# XC95144XL_DEVBOARD.net
KiCad netlist of a schematic drawn in Altium Designer
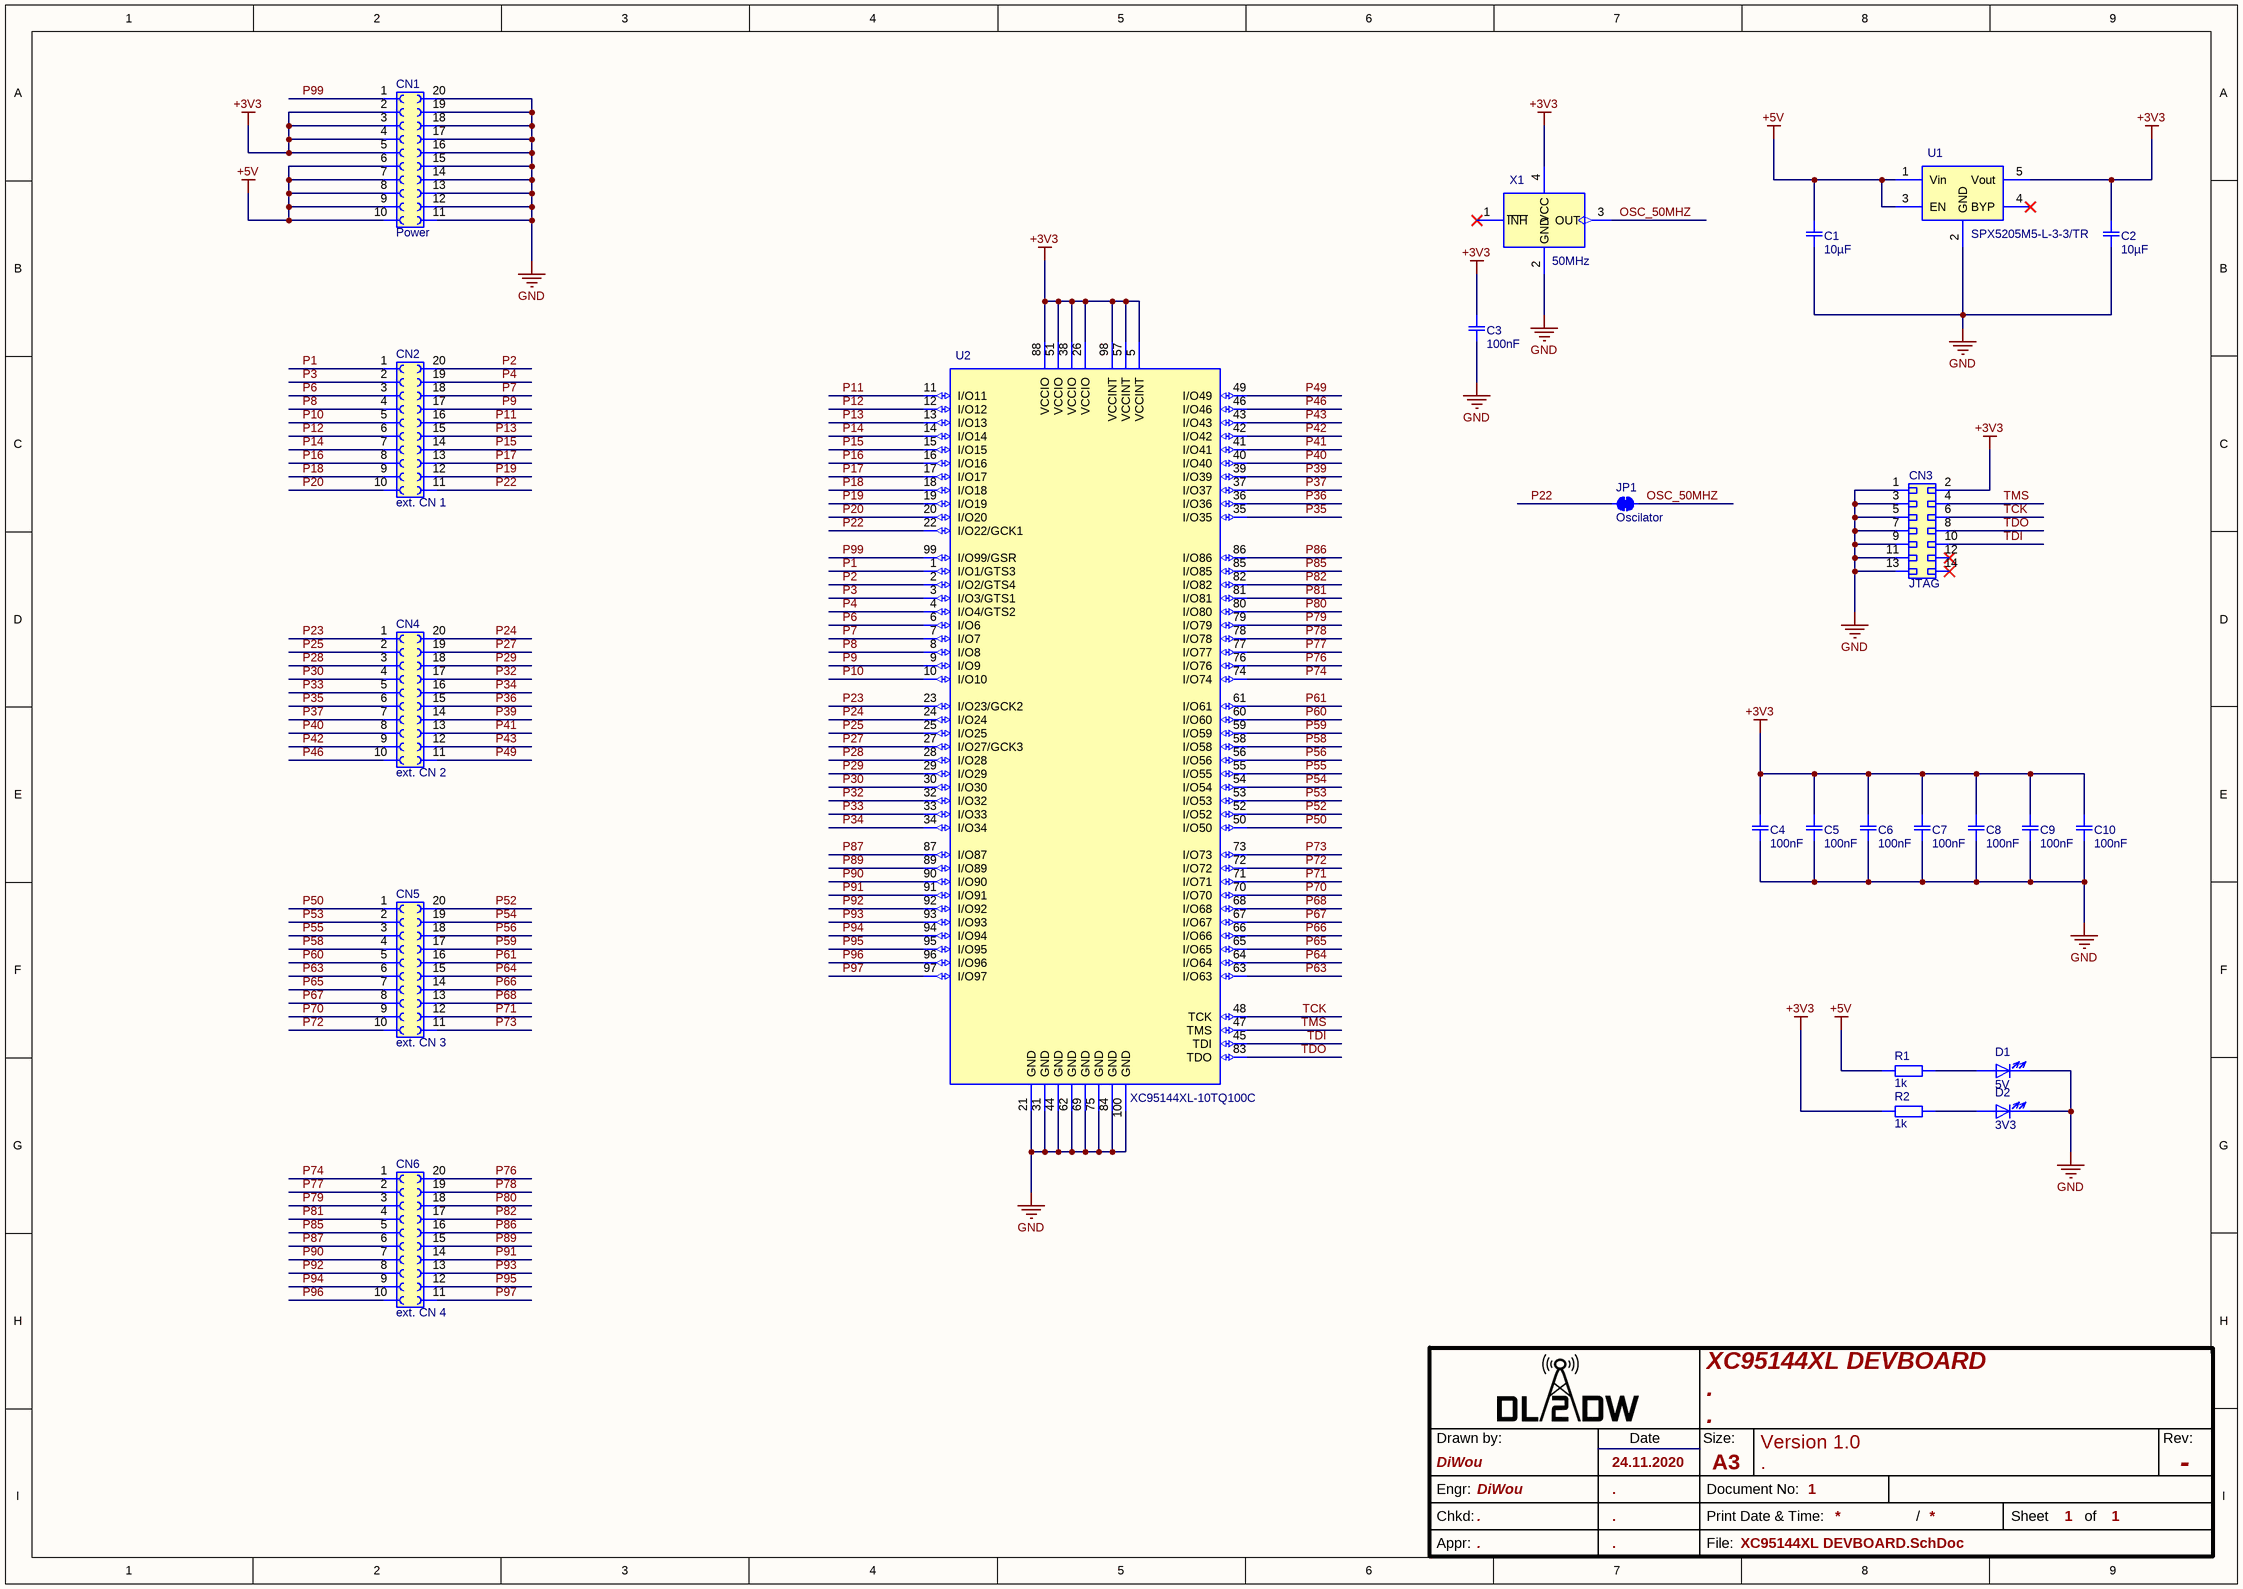
[diagram p0: XC95144XL DEVBOARD.SchDoc]

(export (version "E")
  (design (tool "Eeschema 10.0.6"))
  (components
    (comp (ref "C1")
      (value "10µF")
      (footprint "Kemet C0805CxxxK8RACTU Series H=1.4mm")
      (description "KEMET - C0805C106K8RACTU - CAP, 10µF, 10V, 10%, X7R, 0805")
      (fields (field (name "VOLTAGE") "10V") (field (name "TOLERANCE") "10%"))
      (libsource (lib "PCB-Tech Cloud") (part "Capacitor"))
    )
    (comp (ref "C2")
      (value "10µF")
      (footprint "Kemet C0805CxxxK8RACTU Series H=1.4mm")
      (description "KEMET - C0805C106K8RACTU - CAP, 10µF, 10V, 10%, X7R, 0805")
      (fields (field (name "VOLTAGE") "10V") (field (name "TOLERANCE") "10%"))
      (libsource (lib "PCB-Tech Cloud") (part "Capacitor"))
    )
    (comp (ref "C3")
      (value "100nF")
      (footprint "CAP 100nF SMD 0603 C0603C104J3RACTU")
      (fields (field (name "TOLERANCE") "5%") (field (name "VOLTAGE") "25V"))
      (libsource (lib "PCB-Tech Cloud") (part "Capacitor"))
    )
    (comp (ref "C4")
      (value "100nF")
      (footprint "CAP 100nF SMD 0603 C0603C104J3RACTU")
      (fields (field (name "TOLERANCE") "5%") (field (name "VOLTAGE") "25V"))
      (libsource (lib "PCB-Tech Cloud") (part "Capacitor"))
    )
    (comp (ref "C5")
      (value "100nF")
      (footprint "CAP 100nF SMD 0603 C0603C104J3RACTU")
      (fields (field (name "TOLERANCE") "5%") (field (name "VOLTAGE") "25V"))
      (libsource (lib "PCB-Tech Cloud") (part "Capacitor"))
    )
    (comp (ref "C6")
      (value "100nF")
      (footprint "CAP 100nF SMD 0603 C0603C104J3RACTU")
      (fields (field (name "TOLERANCE") "5%") (field (name "VOLTAGE") "25V"))
      (libsource (lib "PCB-Tech Cloud") (part "Capacitor"))
    )
    (comp (ref "C7")
      (value "100nF")
      (footprint "CAP 100nF SMD 0603 C0603C104J3RACTU")
      (fields (field (name "TOLERANCE") "5%") (field (name "VOLTAGE") "25V"))
      (libsource (lib "PCB-Tech Cloud") (part "Capacitor"))
    )
    (comp (ref "C8")
      (value "100nF")
      (footprint "CAP 100nF SMD 0603 C0603C104J3RACTU")
      (fields (field (name "TOLERANCE") "5%") (field (name "VOLTAGE") "25V"))
      (libsource (lib "PCB-Tech Cloud") (part "Capacitor"))
    )
    (comp (ref "C9")
      (value "100nF")
      (footprint "CAP 100nF SMD 0603 C0603C104J3RACTU")
      (fields (field (name "TOLERANCE") "5%") (field (name "VOLTAGE") "25V"))
      (libsource (lib "PCB-Tech Cloud") (part "Capacitor"))
    )
    (comp (ref "C10")
      (value "100nF")
      (footprint "CAP 100nF SMD 0603 C0603C104J3RACTU")
      (fields (field (name "TOLERANCE") "5%") (field (name "VOLTAGE") "25V"))
      (libsource (lib "PCB-Tech Cloud") (part "Capacitor"))
    )
    (comp (ref "CN1")
      (value "Power")
      (footprint "Female Pin Header 02x10 Straight P2.54mm H8.5mm")
      (description "Headers & Wire Housings 10+10 VERT SOCKET DIL")
      (libsource (lib "PCB-Tech Cloud") (part "CONN Female 02x10"))
    )
    (comp (ref "CN2")
      (value "ext. CN 1")
      (footprint "Female Pin Header 02x10 Straight P2.54mm H8.5mm")
      (description "Headers & Wire Housings 10+10 VERT SOCKET DIL")
      (libsource (lib "PCB-Tech Cloud") (part "CONN Female 02x10"))
    )
    (comp (ref "CN3")
      (value "JTAG")
      (footprint "IDC Header 2x7 P2.54mm Straight")
      (description "Conn Shrouded Header HDR 14 POS 2.54mm Solder ST Thru-Hole")
      (libsource (lib "PCB-Tech Cloud") (part "CONN 02x07 Odd Even"))
    )
    (comp (ref "CN4")
      (value "ext. CN 2")
      (footprint "Female Pin Header 02x10 Straight P2.54mm H8.5mm")
      (description "Headers & Wire Housings 10+10 VERT SOCKET DIL")
      (libsource (lib "PCB-Tech Cloud") (part "CONN Female 02x10"))
    )
    (comp (ref "CN5")
      (value "ext. CN 3")
      (footprint "Female Pin Header 02x10 Straight P2.54mm H8.5mm")
      (description "Headers & Wire Housings 10+10 VERT SOCKET DIL")
      (libsource (lib "PCB-Tech Cloud") (part "CONN Female 02x10"))
    )
    (comp (ref "CN6")
      (value "ext. CN 4")
      (footprint "Female Pin Header 02x10 Straight P2.54mm H8.5mm")
      (description "Headers & Wire Housings 10+10 VERT SOCKET DIL")
      (libsource (lib "PCB-Tech Cloud") (part "CONN Female 02x10"))
    )
    (comp (ref "D1")
      (value "5V")
      (footprint "LED Red SMD 0603")
      (description "LED RED DIFFUSED 0603 SMD")
      (libsource (lib "PCB-Tech Cloud") (part "LED Standard"))
    )
    (comp (ref "D2")
      (value "3V3")
      (footprint "LED Green SMD 0603")
      (description "LED BLUE DIFFUSED 0603 SMD")
      (libsource (lib "PCB-Tech Cloud") (part "LED Standard"))
    )
    (comp (ref "JP1")
      (value "Oscilator")
      (footprint "Solder Jumper Closed")
      (description "Solder Jumper Closed")
      (libsource (lib "PCB-Tech Cloud") (part "Solder Jumper closed"))
    )
    (comp (ref "R1")
      (value "1k")
      (footprint "1k Ohm R 0603 SMD")
      (description "RES SMD 1K OHM 1% 1/10W 0603")
      (fields (field (name "TOLERANCE") "1%"))
      (libsource (lib "PCB-Tech Cloud") (part "Resistor"))
    )
    (comp (ref "R2")
      (value "1k")
      (footprint "1k Ohm R 0603 SMD")
      (description "RES SMD 1K OHM 1% 1/10W 0603")
      (fields (field (name "TOLERANCE") "1%"))
      (libsource (lib "PCB-Tech Cloud") (part "Resistor"))
    )
    (comp (ref "U1")
      (value "SPX5205M5-L-3-3/TR")
      (footprint "SOT-23-5")
      (description "LDO Regulator Pos 3.3V 0.15A 5-Pin SOT-23 T/R")
      (libsource (lib "PCB-Tech Cloud") (part "SPX5205M5-L-3-3/TR"))
    )
    (comp (ref "U2")
      (value "XC95144XL-10TQ100C")
      (footprint "TQFP-100 P0.5mm XC95144XL-7TQ100C")
      (description "IC CPLD 144MC 7.5NS 100TQFP")
      (libsource (lib "PCB-Tech Cloud") (part "XC95144XL-TQG100C"))
    )
    (comp (ref "X1")
      (value "50MHz")
      (footprint "50.000MHZ Oscilator EuroQuartz XO53050UITA")
      (description "XO53050UITA-50.000, Crystal Oscillator, 50 MHz, 50ppm HCMOS, LSTTL 15pF, 4-Pin SMD, 5 x 3.2 x 1mm")
      (libsource (lib "PCB-Tech Cloud") (part "KC5032A16.0000CMGE00"))
    )
  )
  (nets
    (net (code "1") (name "+3V3") (class "Default")
      (node (ref "C10") (pin "2") (pinfunction "2_2") (pintype "passive"))
      (node (ref "C2") (pin "2") (pinfunction "2_2") (pintype "passive"))
      (node (ref "C3") (pin "2") (pinfunction "2_2") (pintype "passive"))
      (node (ref "C4") (pin "2") (pinfunction "2_2") (pintype "passive"))
      (node (ref "C5") (pin "2") (pinfunction "2_2") (pintype "passive"))
      (node (ref "C6") (pin "2") (pinfunction "2_2") (pintype "passive"))
      (node (ref "C7") (pin "2") (pinfunction "2_2") (pintype "passive"))
      (node (ref "C8") (pin "2") (pinfunction "2_2") (pintype "passive"))
      (node (ref "C9") (pin "2") (pinfunction "2_2") (pintype "passive"))
      (node (ref "CN1") (pin "2") (pinfunction "2_2") (pintype "passive"))
      (node (ref "CN1") (pin "3") (pinfunction "3_3") (pintype "passive"))
      (node (ref "CN1") (pin "4") (pinfunction "4_4") (pintype "passive"))
      (node (ref "CN1") (pin "5") (pinfunction "5_5") (pintype "passive"))
      (node (ref "CN3") (pin "2") (pinfunction "2_2") (pintype "passive"))
      (node (ref "R2") (pin "1") (pinfunction "1_1") (pintype "passive"))
      (node (ref "U1") (pin "5") (pinfunction "Vout_5") (pintype "power_in"))
      (node (ref "U2") (pin "26") (pinfunction "VCCIO_26") (pintype "power_in"))
      (node (ref "U2") (pin "38") (pinfunction "VCCIO_38") (pintype "power_in"))
      (node (ref "U2") (pin "5") (pinfunction "VCCINT_5") (pintype "power_in"))
      (node (ref "U2") (pin "51") (pinfunction "VCCIO_51") (pintype "power_in"))
      (node (ref "U2") (pin "57") (pinfunction "VCCINT_57") (pintype "power_in"))
      (node (ref "U2") (pin "88") (pinfunction "VCCIO_88") (pintype "power_in"))
      (node (ref "U2") (pin "98") (pinfunction "VCCINT_98") (pintype "power_in"))
      (node (ref "X1") (pin "4") (pinfunction "VCC_4") (pintype "power_in"))
    )
    (net (code "2") (name "+5V") (class "Default")
      (node (ref "C1") (pin "2") (pinfunction "2_2") (pintype "passive"))
      (node (ref "CN1") (pin "10") (pinfunction "10_10") (pintype "passive"))
      (node (ref "CN1") (pin "6") (pinfunction "6_6") (pintype "passive"))
      (node (ref "CN1") (pin "7") (pinfunction "7_7") (pintype "passive"))
      (node (ref "CN1") (pin "8") (pinfunction "8_8") (pintype "passive"))
      (node (ref "CN1") (pin "9") (pinfunction "9_9") (pintype "passive"))
      (node (ref "R1") (pin "1") (pinfunction "1_1") (pintype "passive"))
      (node (ref "U1") (pin "1") (pinfunction "Vin_1") (pintype "power_in"))
      (node (ref "U1") (pin "3") (pinfunction "EN_3") (pintype "passive"))
    )
    (net (code "3") (name "/OSC_50MHZ") (class "Default")
      (node (ref "JP1") (pin "2") (pinfunction "2_2") (pintype "passive"))
      (node (ref "X1") (pin "3") (pinfunction "OUT_3") (pintype "output"))
    )
    (net (code "4") (name "/P1") (class "Default")
      (node (ref "CN2") (pin "1") (pinfunction "1_1") (pintype "passive"))
      (node (ref "U2") (pin "1") (pinfunction "I/O1/GTS3_1") (pintype "bidirectional"))
    )
    (net (code "5") (name "/P2") (class "Default")
      (node (ref "CN2") (pin "20") (pinfunction "20_20") (pintype "passive"))
      (node (ref "U2") (pin "2") (pinfunction "I/O2/GTS4_2") (pintype "bidirectional"))
    )
    (net (code "6") (name "/P3") (class "Default")
      (node (ref "CN2") (pin "2") (pinfunction "2_2") (pintype "passive"))
      (node (ref "U2") (pin "3") (pinfunction "I/O3/GTS1_3") (pintype "bidirectional"))
    )
    (net (code "7") (name "/P4") (class "Default")
      (node (ref "CN2") (pin "19") (pinfunction "19_19") (pintype "passive"))
      (node (ref "U2") (pin "4") (pinfunction "I/O4/GTS2_4") (pintype "bidirectional"))
    )
    (net (code "8") (name "/P6") (class "Default")
      (node (ref "CN2") (pin "3") (pinfunction "3_3") (pintype "passive"))
      (node (ref "U2") (pin "6") (pinfunction "I/O6_6") (pintype "bidirectional"))
    )
    (net (code "9") (name "/P7") (class "Default")
      (node (ref "CN2") (pin "18") (pinfunction "18_18") (pintype "passive"))
      (node (ref "U2") (pin "7") (pinfunction "I/O7_7") (pintype "bidirectional"))
    )
    (net (code "10") (name "/P8") (class "Default")
      (node (ref "CN2") (pin "4") (pinfunction "4_4") (pintype "passive"))
      (node (ref "U2") (pin "8") (pinfunction "I/O8_8") (pintype "bidirectional"))
    )
    (net (code "11") (name "/P9") (class "Default")
      (node (ref "CN2") (pin "17") (pinfunction "17_17") (pintype "passive"))
      (node (ref "U2") (pin "9") (pinfunction "I/O9_9") (pintype "bidirectional"))
    )
    (net (code "12") (name "/P10") (class "Default")
      (node (ref "CN2") (pin "5") (pinfunction "5_5") (pintype "passive"))
      (node (ref "U2") (pin "10") (pinfunction "I/O10_10") (pintype "bidirectional"))
    )
    (net (code "13") (name "/P11") (class "Default")
      (node (ref "CN2") (pin "16") (pinfunction "16_16") (pintype "passive"))
      (node (ref "U2") (pin "11") (pinfunction "I/O11_11") (pintype "bidirectional"))
    )
    (net (code "14") (name "/P12") (class "Default")
      (node (ref "CN2") (pin "6") (pinfunction "6_6") (pintype "passive"))
      (node (ref "U2") (pin "12") (pinfunction "I/O12_12") (pintype "bidirectional"))
    )
    (net (code "15") (name "/P13") (class "Default")
      (node (ref "CN2") (pin "15") (pinfunction "15_15") (pintype "passive"))
      (node (ref "U2") (pin "13") (pinfunction "I/O13_13") (pintype "bidirectional"))
    )
    (net (code "16") (name "/P14") (class "Default")
      (node (ref "CN2") (pin "7") (pinfunction "7_7") (pintype "passive"))
      (node (ref "U2") (pin "14") (pinfunction "I/O14_14") (pintype "bidirectional"))
    )
    (net (code "17") (name "/P15") (class "Default")
      (node (ref "CN2") (pin "14") (pinfunction "14_14") (pintype "passive"))
      (node (ref "U2") (pin "15") (pinfunction "I/O15_15") (pintype "bidirectional"))
    )
    (net (code "18") (name "/P16") (class "Default")
      (node (ref "CN2") (pin "8") (pinfunction "8_8") (pintype "passive"))
      (node (ref "U2") (pin "16") (pinfunction "I/O16_16") (pintype "bidirectional"))
    )
    (net (code "19") (name "/P17") (class "Default")
      (node (ref "CN2") (pin "13") (pinfunction "13_13") (pintype "passive"))
      (node (ref "U2") (pin "17") (pinfunction "I/O17_17") (pintype "bidirectional"))
    )
    (net (code "20") (name "/P18") (class "Default")
      (node (ref "CN2") (pin "9") (pinfunction "9_9") (pintype "passive"))
      (node (ref "U2") (pin "18") (pinfunction "I/O18_18") (pintype "bidirectional"))
    )
    (net (code "21") (name "/P19") (class "Default")
      (node (ref "CN2") (pin "12") (pinfunction "12_12") (pintype "passive"))
      (node (ref "U2") (pin "19") (pinfunction "I/O19_19") (pintype "bidirectional"))
    )
    (net (code "22") (name "/P20") (class "Default")
      (node (ref "CN2") (pin "10") (pinfunction "10_10") (pintype "passive"))
      (node (ref "U2") (pin "20") (pinfunction "I/O20_20") (pintype "bidirectional"))
    )
    (net (code "23") (name "/P22") (class "Default")
      (node (ref "CN2") (pin "11") (pinfunction "11_11") (pintype "passive"))
      (node (ref "JP1") (pin "1") (pinfunction "1_1") (pintype "passive"))
      (node (ref "U2") (pin "22") (pinfunction "I/O22/GCK1_22") (pintype "bidirectional"))
    )
    (net (code "24") (name "/P23") (class "Default")
      (node (ref "CN4") (pin "1") (pinfunction "1_1") (pintype "passive"))
      (node (ref "U2") (pin "23") (pinfunction "I/O23/GCK2_23") (pintype "bidirectional"))
    )
    (net (code "25") (name "/P24") (class "Default")
      (node (ref "CN4") (pin "20") (pinfunction "20_20") (pintype "passive"))
      (node (ref "U2") (pin "24") (pinfunction "I/O24_24") (pintype "bidirectional"))
    )
    (net (code "26") (name "/P25") (class "Default")
      (node (ref "CN4") (pin "2") (pinfunction "2_2") (pintype "passive"))
      (node (ref "U2") (pin "25") (pinfunction "I/O25_25") (pintype "bidirectional"))
    )
    (net (code "27") (name "/P27") (class "Default")
      (node (ref "CN4") (pin "19") (pinfunction "19_19") (pintype "passive"))
      (node (ref "U2") (pin "27") (pinfunction "I/O27/GCK3_27") (pintype "bidirectional"))
    )
    (net (code "28") (name "/P28") (class "Default")
      (node (ref "CN4") (pin "3") (pinfunction "3_3") (pintype "passive"))
      (node (ref "U2") (pin "28") (pinfunction "I/O28_28") (pintype "bidirectional"))
    )
    (net (code "29") (name "/P29") (class "Default")
      (node (ref "CN4") (pin "18") (pinfunction "18_18") (pintype "passive"))
      (node (ref "U2") (pin "29") (pinfunction "I/O29_29") (pintype "bidirectional"))
    )
    (net (code "30") (name "/P30") (class "Default")
      (node (ref "CN4") (pin "4") (pinfunction "4_4") (pintype "passive"))
      (node (ref "U2") (pin "30") (pinfunction "I/O30_30") (pintype "bidirectional"))
    )
    (net (code "31") (name "/P32") (class "Default")
      (node (ref "CN4") (pin "17") (pinfunction "17_17") (pintype "passive"))
      (node (ref "U2") (pin "32") (pinfunction "I/O32_32") (pintype "bidirectional"))
    )
    (net (code "32") (name "/P33") (class "Default")
      (node (ref "CN4") (pin "5") (pinfunction "5_5") (pintype "passive"))
      (node (ref "U2") (pin "33") (pinfunction "I/O33_33") (pintype "bidirectional"))
    )
    (net (code "33") (name "/P34") (class "Default")
      (node (ref "CN4") (pin "16") (pinfunction "16_16") (pintype "passive"))
      (node (ref "U2") (pin "34") (pinfunction "I/O34_34") (pintype "bidirectional"))
    )
    (net (code "34") (name "/P35") (class "Default")
      (node (ref "CN4") (pin "6") (pinfunction "6_6") (pintype "passive"))
      (node (ref "U2") (pin "35") (pinfunction "I/O35_35") (pintype "bidirectional"))
    )
    (net (code "35") (name "/P36") (class "Default")
      (node (ref "CN4") (pin "15") (pinfunction "15_15") (pintype "passive"))
      (node (ref "U2") (pin "36") (pinfunction "I/O36_36") (pintype "bidirectional"))
    )
    (net (code "36") (name "/P37") (class "Default")
      (node (ref "CN4") (pin "7") (pinfunction "7_7") (pintype "passive"))
      (node (ref "U2") (pin "37") (pinfunction "I/O37_37") (pintype "bidirectional"))
    )
    (net (code "37") (name "/P39") (class "Default")
      (node (ref "CN4") (pin "14") (pinfunction "14_14") (pintype "passive"))
      (node (ref "U2") (pin "39") (pinfunction "I/O39_39") (pintype "bidirectional"))
    )
    (net (code "38") (name "/P40") (class "Default")
      (node (ref "CN4") (pin "8") (pinfunction "8_8") (pintype "passive"))
      (node (ref "U2") (pin "40") (pinfunction "I/O40_40") (pintype "bidirectional"))
    )
    (net (code "39") (name "/P41") (class "Default")
      (node (ref "CN4") (pin "13") (pinfunction "13_13") (pintype "passive"))
      (node (ref "U2") (pin "41") (pinfunction "I/O41_41") (pintype "bidirectional"))
    )
    (net (code "40") (name "/P42") (class "Default")
      (node (ref "CN4") (pin "9") (pinfunction "9_9") (pintype "passive"))
      (node (ref "U2") (pin "42") (pinfunction "I/O42_42") (pintype "bidirectional"))
    )
    (net (code "41") (name "/P43") (class "Default")
      (node (ref "CN4") (pin "12") (pinfunction "12_12") (pintype "passive"))
      (node (ref "U2") (pin "43") (pinfunction "I/O43_43") (pintype "bidirectional"))
    )
    (net (code "42") (name "/P46") (class "Default")
      (node (ref "CN4") (pin "10") (pinfunction "10_10") (pintype "passive"))
      (node (ref "U2") (pin "46") (pinfunction "I/O46_46") (pintype "bidirectional"))
    )
    (net (code "43") (name "/P49") (class "Default")
      (node (ref "CN4") (pin "11") (pinfunction "11_11") (pintype "passive"))
      (node (ref "U2") (pin "49") (pinfunction "I/O49_49") (pintype "bidirectional"))
    )
    (net (code "44") (name "/P50") (class "Default")
      (node (ref "CN5") (pin "1") (pinfunction "1_1") (pintype "passive"))
      (node (ref "U2") (pin "50") (pinfunction "I/O50_50") (pintype "bidirectional"))
    )
    (net (code "45") (name "/P52") (class "Default")
      (node (ref "CN5") (pin "20") (pinfunction "20_20") (pintype "passive"))
      (node (ref "U2") (pin "52") (pinfunction "I/O52_52") (pintype "bidirectional"))
    )
    (net (code "46") (name "/P53") (class "Default")
      (node (ref "CN5") (pin "2") (pinfunction "2_2") (pintype "passive"))
      (node (ref "U2") (pin "53") (pinfunction "I/O53_53") (pintype "bidirectional"))
    )
    (net (code "47") (name "/P54") (class "Default")
      (node (ref "CN5") (pin "19") (pinfunction "19_19") (pintype "passive"))
      (node (ref "U2") (pin "54") (pinfunction "I/O54_54") (pintype "bidirectional"))
    )
    (net (code "48") (name "/P55") (class "Default")
      (node (ref "CN5") (pin "3") (pinfunction "3_3") (pintype "passive"))
      (node (ref "U2") (pin "55") (pinfunction "I/O55_55") (pintype "bidirectional"))
    )
    (net (code "49") (name "/P56") (class "Default")
      (node (ref "CN5") (pin "18") (pinfunction "18_18") (pintype "passive"))
      (node (ref "U2") (pin "56") (pinfunction "I/O56_56") (pintype "bidirectional"))
    )
    (net (code "50") (name "/P58") (class "Default")
      (node (ref "CN5") (pin "4") (pinfunction "4_4") (pintype "passive"))
      (node (ref "U2") (pin "58") (pinfunction "I/O58_58") (pintype "bidirectional"))
    )
    (net (code "51") (name "/P59") (class "Default")
      (node (ref "CN5") (pin "17") (pinfunction "17_17") (pintype "passive"))
      (node (ref "U2") (pin "59") (pinfunction "I/O59_59") (pintype "bidirectional"))
    )
    (net (code "52") (name "/P60") (class "Default")
      (node (ref "CN5") (pin "5") (pinfunction "5_5") (pintype "passive"))
      (node (ref "U2") (pin "60") (pinfunction "I/O60_60") (pintype "bidirectional"))
    )
    (net (code "53") (name "/P61") (class "Default")
      (node (ref "CN5") (pin "16") (pinfunction "16_16") (pintype "passive"))
      (node (ref "U2") (pin "61") (pinfunction "I/O61_61") (pintype "bidirectional"))
    )
    (net (code "54") (name "/P63") (class "Default")
      (node (ref "CN5") (pin "6") (pinfunction "6_6") (pintype "passive"))
      (node (ref "U2") (pin "63") (pinfunction "I/O63_63") (pintype "bidirectional"))
    )
    (net (code "55") (name "/P64") (class "Default")
      (node (ref "CN5") (pin "15") (pinfunction "15_15") (pintype "passive"))
      (node (ref "U2") (pin "64") (pinfunction "I/O64_64") (pintype "bidirectional"))
    )
    (net (code "56") (name "/P65") (class "Default")
      (node (ref "CN5") (pin "7") (pinfunction "7_7") (pintype "passive"))
      (node (ref "U2") (pin "65") (pinfunction "I/O65_65") (pintype "bidirectional"))
    )
    (net (code "57") (name "/P66") (class "Default")
      (node (ref "CN5") (pin "14") (pinfunction "14_14") (pintype "passive"))
      (node (ref "U2") (pin "66") (pinfunction "I/O66_66") (pintype "bidirectional"))
    )
    (net (code "58") (name "/P67") (class "Default")
      (node (ref "CN5") (pin "8") (pinfunction "8_8") (pintype "passive"))
      (node (ref "U2") (pin "67") (pinfunction "I/O67_67") (pintype "bidirectional"))
    )
    (net (code "59") (name "/P68") (class "Default")
      (node (ref "CN5") (pin "13") (pinfunction "13_13") (pintype "passive"))
      (node (ref "U2") (pin "68") (pinfunction "I/O68_68") (pintype "bidirectional"))
    )
    (net (code "60") (name "/P70") (class "Default")
      (node (ref "CN5") (pin "9") (pinfunction "9_9") (pintype "passive"))
      (node (ref "U2") (pin "70") (pinfunction "I/O70_70") (pintype "bidirectional"))
    )
    (net (code "61") (name "/P71") (class "Default")
      (node (ref "CN5") (pin "12") (pinfunction "12_12") (pintype "passive"))
      (node (ref "U2") (pin "71") (pinfunction "I/O71_71") (pintype "bidirectional"))
    )
    (net (code "62") (name "/P72") (class "Default")
      (node (ref "CN5") (pin "10") (pinfunction "10_10") (pintype "passive"))
      (node (ref "U2") (pin "72") (pinfunction "I/O72_72") (pintype "bidirectional"))
    )
    (net (code "63") (name "/P73") (class "Default")
      (node (ref "CN5") (pin "11") (pinfunction "11_11") (pintype "passive"))
      (node (ref "U2") (pin "73") (pinfunction "I/O73_73") (pintype "bidirectional"))
    )
    (net (code "64") (name "/P74") (class "Default")
      (node (ref "CN6") (pin "1") (pinfunction "1_1") (pintype "passive"))
      (node (ref "U2") (pin "74") (pinfunction "I/O74_74") (pintype "bidirectional"))
    )
    (net (code "65") (name "/P76") (class "Default")
      (node (ref "CN6") (pin "20") (pinfunction "20_20") (pintype "passive"))
      (node (ref "U2") (pin "76") (pinfunction "I/O76_76") (pintype "bidirectional"))
    )
    (net (code "66") (name "/P77") (class "Default")
      (node (ref "CN6") (pin "2") (pinfunction "2_2") (pintype "passive"))
      (node (ref "U2") (pin "77") (pinfunction "I/O77_77") (pintype "bidirectional"))
    )
    (net (code "67") (name "/P78") (class "Default")
      (node (ref "CN6") (pin "19") (pinfunction "19_19") (pintype "passive"))
      (node (ref "U2") (pin "78") (pinfunction "I/O78_78") (pintype "bidirectional"))
    )
    (net (code "68") (name "/P79") (class "Default")
      (node (ref "CN6") (pin "3") (pinfunction "3_3") (pintype "passive"))
      (node (ref "U2") (pin "79") (pinfunction "I/O79_79") (pintype "bidirectional"))
    )
    (net (code "69") (name "/P80") (class "Default")
      (node (ref "CN6") (pin "18") (pinfunction "18_18") (pintype "passive"))
      (node (ref "U2") (pin "80") (pinfunction "I/O80_80") (pintype "bidirectional"))
    )
    (net (code "70") (name "/P81") (class "Default")
      (node (ref "CN6") (pin "4") (pinfunction "4_4") (pintype "passive"))
      (node (ref "U2") (pin "81") (pinfunction "I/O81_81") (pintype "bidirectional"))
    )
    (net (code "71") (name "/P82") (class "Default")
      (node (ref "CN6") (pin "17") (pinfunction "17_17") (pintype "passive"))
      (node (ref "U2") (pin "82") (pinfunction "I/O82_82") (pintype "bidirectional"))
    )
    (net (code "72") (name "/P85") (class "Default")
      (node (ref "CN6") (pin "5") (pinfunction "5_5") (pintype "passive"))
      (node (ref "U2") (pin "85") (pinfunction "I/O85_85") (pintype "bidirectional"))
    )
    (net (code "73") (name "/P86") (class "Default")
      (node (ref "CN6") (pin "16") (pinfunction "16_16") (pintype "passive"))
      (node (ref "U2") (pin "86") (pinfunction "I/O86_86") (pintype "bidirectional"))
    )
    (net (code "74") (name "/P87") (class "Default")
      (node (ref "CN6") (pin "6") (pinfunction "6_6") (pintype "passive"))
      (node (ref "U2") (pin "87") (pinfunction "I/O87_87") (pintype "bidirectional"))
    )
    (net (code "75") (name "/P89") (class "Default")
      (node (ref "CN6") (pin "15") (pinfunction "15_15") (pintype "passive"))
      (node (ref "U2") (pin "89") (pinfunction "I/O89_89") (pintype "bidirectional"))
    )
    (net (code "76") (name "/P90") (class "Default")
      (node (ref "CN6") (pin "7") (pinfunction "7_7") (pintype "passive"))
      (node (ref "U2") (pin "90") (pinfunction "I/O90_90") (pintype "bidirectional"))
    )
    (net (code "77") (name "/P91") (class "Default")
      (node (ref "CN6") (pin "14") (pinfunction "14_14") (pintype "passive"))
      (node (ref "U2") (pin "91") (pinfunction "I/O91_91") (pintype "bidirectional"))
    )
    (net (code "78") (name "/P92") (class "Default")
      (node (ref "CN6") (pin "8") (pinfunction "8_8") (pintype "passive"))
      (node (ref "U2") (pin "92") (pinfunction "I/O92_92") (pintype "bidirectional"))
    )
    (net (code "79") (name "/P93") (class "Default")
      (node (ref "CN6") (pin "13") (pinfunction "13_13") (pintype "passive"))
      (node (ref "U2") (pin "93") (pinfunction "I/O93_93") (pintype "bidirectional"))
    )
    (net (code "80") (name "/P94") (class "Default")
      (node (ref "CN6") (pin "9") (pinfunction "9_9") (pintype "passive"))
      (node (ref "U2") (pin "94") (pinfunction "I/O94_94") (pintype "bidirectional"))
    )
    (net (code "81") (name "/P95") (class "Default")
      (node (ref "CN6") (pin "12") (pinfunction "12_12") (pintype "passive"))
      (node (ref "U2") (pin "95") (pinfunction "I/O95_95") (pintype "bidirectional"))
    )
    (net (code "82") (name "/P96") (class "Default")
      (node (ref "CN6") (pin "10") (pinfunction "10_10") (pintype "passive"))
      (node (ref "U2") (pin "96") (pinfunction "I/O96_96") (pintype "bidirectional"))
    )
    (net (code "83") (name "/P97") (class "Default")
      (node (ref "CN6") (pin "11") (pinfunction "11_11") (pintype "passive"))
      (node (ref "U2") (pin "97") (pinfunction "I/O97_97") (pintype "bidirectional"))
    )
    (net (code "84") (name "/P99") (class "Default")
      (node (ref "CN1") (pin "1") (pinfunction "1_1") (pintype "passive"))
      (node (ref "U2") (pin "99") (pinfunction "I/O99/GSR_99") (pintype "bidirectional"))
    )
    (net (code "85") (name "/TCK") (class "Default")
      (node (ref "CN3") (pin "6") (pinfunction "6_6") (pintype "passive"))
      (node (ref "U2") (pin "48") (pinfunction "TCK_48") (pintype "bidirectional"))
    )
    (net (code "86") (name "/TDI") (class "Default")
      (node (ref "CN3") (pin "10") (pinfunction "10_10") (pintype "passive"))
      (node (ref "U2") (pin "45") (pinfunction "TDI_45") (pintype "bidirectional"))
    )
    (net (code "87") (name "/TDO") (class "Default")
      (node (ref "CN3") (pin "8") (pinfunction "8_8") (pintype "passive"))
      (node (ref "U2") (pin "83") (pinfunction "TDO_83") (pintype "bidirectional"))
    )
    (net (code "88") (name "/TMS") (class "Default")
      (node (ref "CN3") (pin "4") (pinfunction "4_4") (pintype "passive"))
      (node (ref "U2") (pin "47") (pinfunction "TMS_47") (pintype "bidirectional"))
    )
    (net (code "89") (name "GND") (class "Default")
      (node (ref "C1") (pin "1") (pinfunction "1_1") (pintype "passive"))
      (node (ref "C10") (pin "1") (pinfunction "1_1") (pintype "passive"))
      (node (ref "C2") (pin "1") (pinfunction "1_1") (pintype "passive"))
      (node (ref "C3") (pin "1") (pinfunction "1_1") (pintype "passive"))
      (node (ref "C4") (pin "1") (pinfunction "1_1") (pintype "passive"))
      (node (ref "C5") (pin "1") (pinfunction "1_1") (pintype "passive"))
      (node (ref "C6") (pin "1") (pinfunction "1_1") (pintype "passive"))
      (node (ref "C7") (pin "1") (pinfunction "1_1") (pintype "passive"))
      (node (ref "C8") (pin "1") (pinfunction "1_1") (pintype "passive"))
      (node (ref "C9") (pin "1") (pinfunction "1_1") (pintype "passive"))
      (node (ref "CN1") (pin "11") (pinfunction "11_11") (pintype "passive"))
      (node (ref "CN1") (pin "12") (pinfunction "12_12") (pintype "passive"))
      (node (ref "CN1") (pin "13") (pinfunction "13_13") (pintype "passive"))
      (node (ref "CN1") (pin "14") (pinfunction "14_14") (pintype "passive"))
      (node (ref "CN1") (pin "15") (pinfunction "15_15") (pintype "passive"))
      (node (ref "CN1") (pin "16") (pinfunction "16_16") (pintype "passive"))
      (node (ref "CN1") (pin "17") (pinfunction "17_17") (pintype "passive"))
      (node (ref "CN1") (pin "18") (pinfunction "18_18") (pintype "passive"))
      (node (ref "CN1") (pin "19") (pinfunction "19_19") (pintype "passive"))
      (node (ref "CN1") (pin "20") (pinfunction "20_20") (pintype "passive"))
      (node (ref "CN3") (pin "1") (pinfunction "1_1") (pintype "passive"))
      (node (ref "CN3") (pin "11") (pinfunction "11_11") (pintype "passive"))
      (node (ref "CN3") (pin "13") (pinfunction "13_13") (pintype "passive"))
      (node (ref "CN3") (pin "3") (pinfunction "3_3") (pintype "passive"))
      (node (ref "CN3") (pin "5") (pinfunction "5_5") (pintype "passive"))
      (node (ref "CN3") (pin "7") (pinfunction "7_7") (pintype "passive"))
      (node (ref "CN3") (pin "9") (pinfunction "9_9") (pintype "passive"))
      (node (ref "D1") (pin "1") (pinfunction "1_1") (pintype "passive"))
      (node (ref "D2") (pin "1") (pinfunction "1_1") (pintype "passive"))
      (node (ref "U1") (pin "2") (pinfunction "GND_2") (pintype "power_in"))
      (node (ref "U2") (pin "100") (pinfunction "GND_100") (pintype "passive"))
      (node (ref "U2") (pin "21") (pinfunction "GND_21") (pintype "passive"))
      (node (ref "U2") (pin "31") (pinfunction "GND_31") (pintype "passive"))
      (node (ref "U2") (pin "44") (pinfunction "GND_44") (pintype "passive"))
      (node (ref "U2") (pin "62") (pinfunction "GND_62") (pintype "passive"))
      (node (ref "U2") (pin "69") (pinfunction "GND_69") (pintype "passive"))
      (node (ref "U2") (pin "75") (pinfunction "GND_75") (pintype "passive"))
      (node (ref "U2") (pin "84") (pinfunction "GND_84") (pintype "passive"))
      (node (ref "X1") (pin "2") (pinfunction "GND_2") (pintype "passive"))
    )
    (net (code "90") (name "Net-(D1-Pad2)") (class "Default")
      (node (ref "D1") (pin "2") (pinfunction "2_2") (pintype "passive"))
      (node (ref "R1") (pin "2") (pinfunction "2_2") (pintype "passive"))
    )
    (net (code "91") (name "Net-(D2-Pad2)") (class "Default")
      (node (ref "D2") (pin "2") (pinfunction "2_2") (pintype "passive"))
      (node (ref "R2") (pin "2") (pinfunction "2_2") (pintype "passive"))
    )
    (net (code "92") (name "unconnected-(CN3-Pad12)") (class "Default")
      (node (ref "CN3") (pin "12") (pinfunction "12_12") (pintype "passive+no_connect"))
    )
    (net (code "93") (name "unconnected-(CN3-Pad14)") (class "Default")
      (node (ref "CN3") (pin "14") (pinfunction "14_14") (pintype "passive+no_connect"))
    )
    (net (code "94") (name "unconnected-(U1-BYP-Pad4)") (class "Default")
      (node (ref "U1") (pin "4") (pinfunction "BYP_4") (pintype "passive+no_connect"))
    )
    (net (code "95") (name "unconnected-(X1-~{INH}-Pad1)") (class "Default")
      (node (ref "X1") (pin "1") (pinfunction "~{INH}_1") (pintype "passive+no_connect"))
    )
  )
)
